# TouScruino-ui1-v0.net
KiCad netlist of a schematic drawn in EAGLE
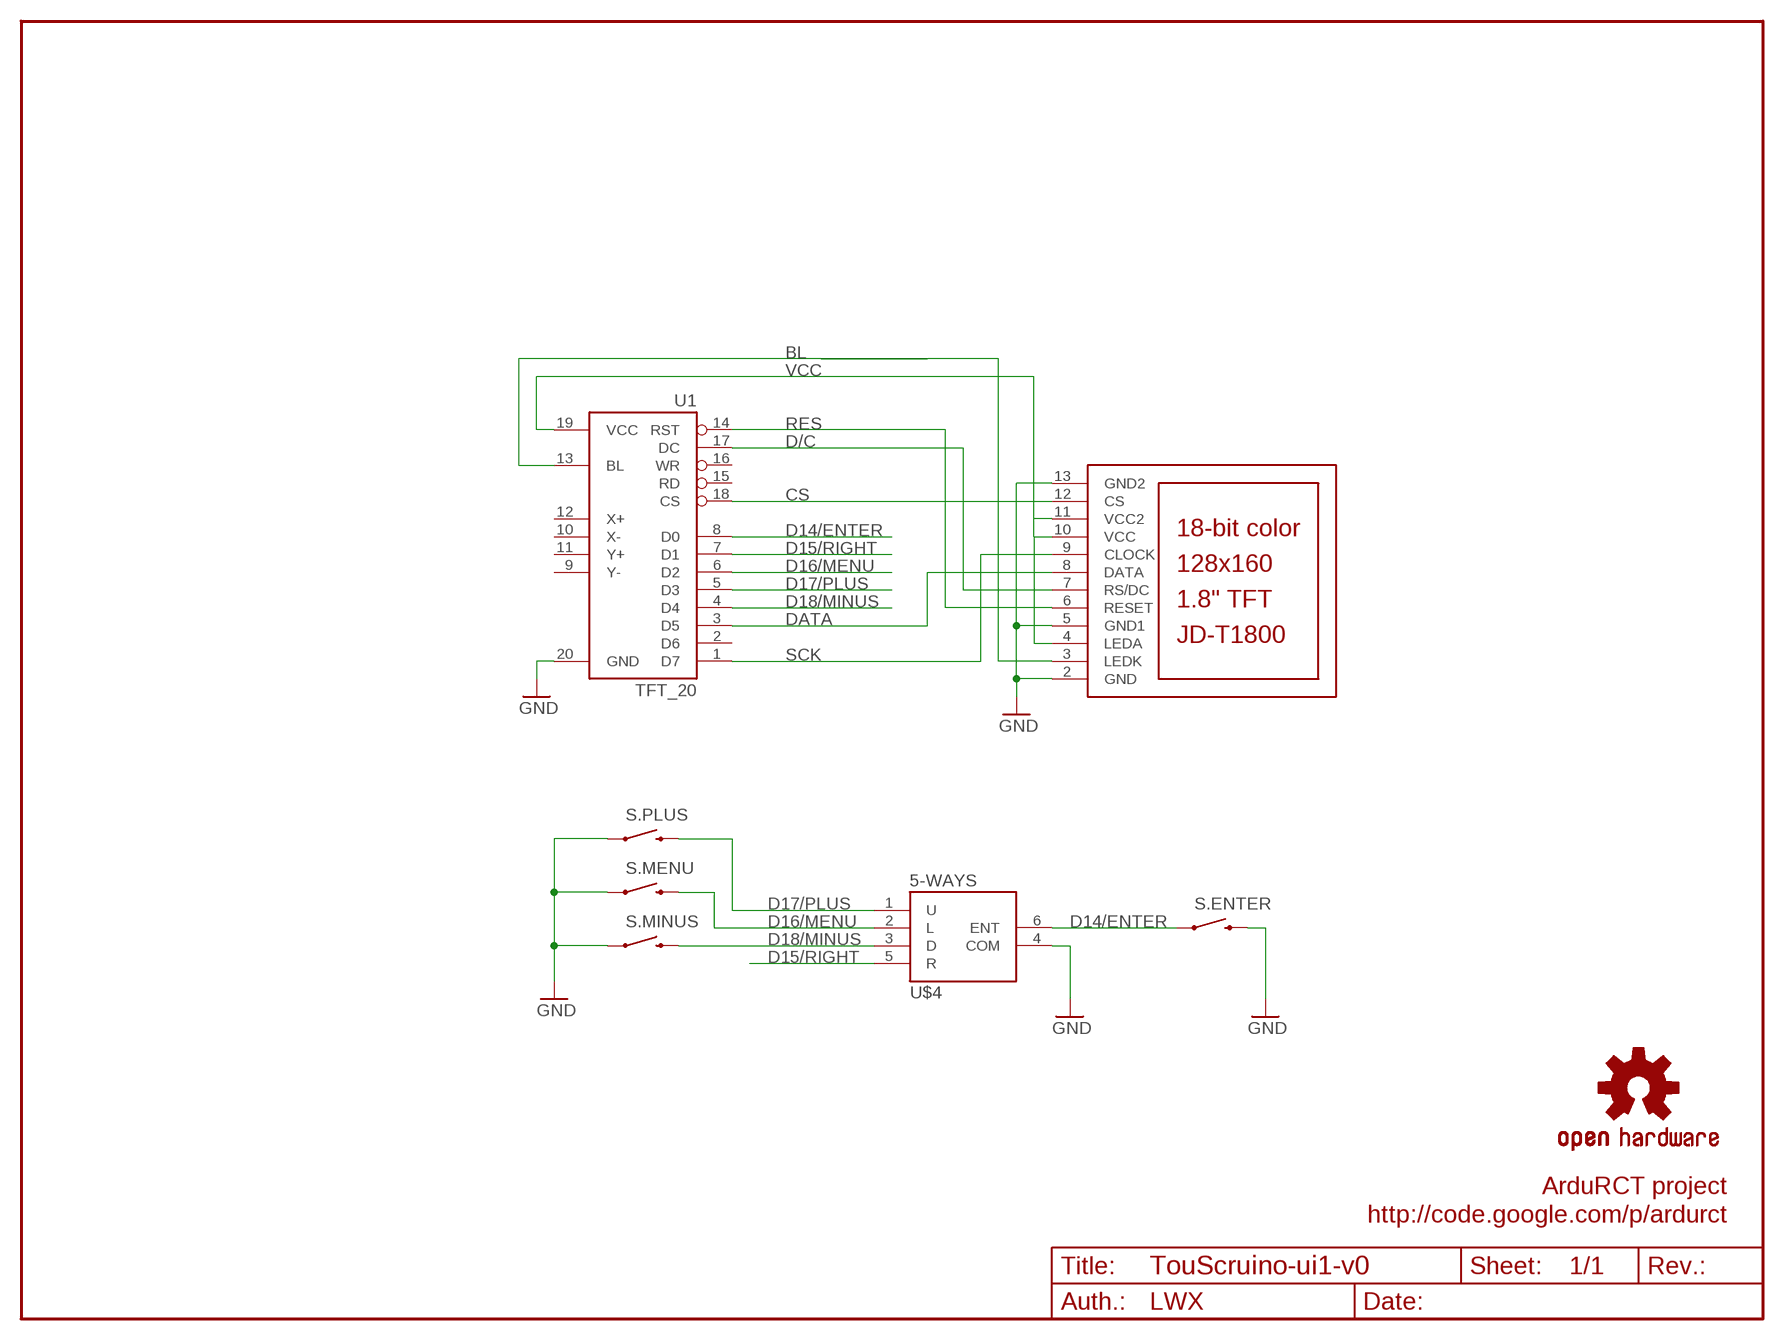
[diagram p0: schematic, sheet 1]

(export (version "E")
  (design (tool "Eeschema 10.0.6"))
  (components
    (comp (ref "LCD1")
      (value "JD-T1800")
      (footprint "eagle-import:JD-T1800")
      (libsource (lib "eagle-import") (part "JD-T1800"))
    )
    (comp (ref "S.ENTER")
      (value "SWITCH_SMD")
      (footprint "eagle-import:TACTILE_SWITCH_SMD")
      (libsource (lib "eagle-import") (part "SWITCH_SMD"))
    )
    (comp (ref "S.MENU")
      (value "SWITCH_SMD")
      (footprint "eagle-import:TACTILE_SWITCH_SMD")
      (libsource (lib "eagle-import") (part "SWITCH_SMD"))
    )
    (comp (ref "S.MINUS")
      (value "SWITCH_SMD")
      (footprint "eagle-import:TACTILE_SWITCH_SMD")
      (libsource (lib "eagle-import") (part "SWITCH_SMD"))
    )
    (comp (ref "S.PLUS")
      (value "SWITCH_SMD")
      (footprint "eagle-import:TACTILE_SWITCH_SMD")
      (libsource (lib "eagle-import") (part "SWITCH_SMD"))
    )
    (comp (ref "U$3")
      (value "OSHW-LOGOM")
      (footprint "eagle-import:OSHW-LOGO-M")
      (libsource (lib "eagle-import") (part "OSHW-LOGOM"))
    )
    (comp (ref "U$4")
      (value "5-WAYS")
      (footprint "eagle-import:5-WAYS_ALPS")
      (libsource (lib "eagle-import") (part "5-WAYS"))
    )
    (comp (ref "U1")
      (value "TFT_20")
      (footprint "eagle-import:TFT_20")
      (libsource (lib "eagle-import") (part "TFT_20"))
    )
  )
  (nets
    (net (code "1") (name "/BL") (class "Default")
      (node (ref "LCD1") (pin "3") (pinfunction "LEDK_3") (pintype "input"))
      (node (ref "U1") (pin "13") (pinfunction "BL_13") (pintype "bidirectional"))
    )
    (net (code "2") (name "/CS") (class "Default")
      (node (ref "LCD1") (pin "12") (pinfunction "CS_12") (pintype "input"))
      (node (ref "U1") (pin "18") (pinfunction "CS_18") (pintype "bidirectional"))
    )
    (net (code "3") (name "/D14{slash}ENTER") (class "Default")
      (node (ref "S.ENTER") (pin "1") (pinfunction "1_1") (pintype "passive"))
      (node (ref "U$4") (pin "6") (pinfunction "ENT_6") (pintype "bidirectional"))
      (node (ref "U1") (pin "8") (pinfunction "D0_8") (pintype "bidirectional"))
    )
    (net (code "4") (name "/D15{slash}RIGHT") (class "Default")
      (node (ref "U$4") (pin "5") (pinfunction "R_5") (pintype "bidirectional"))
      (node (ref "U1") (pin "7") (pinfunction "D1_7") (pintype "bidirectional"))
    )
    (net (code "5") (name "/D16{slash}MENU") (class "Default")
      (node (ref "S.MENU") (pin "3") (pinfunction "2_3") (pintype "passive"))
      (node (ref "U$4") (pin "2") (pinfunction "L_2") (pintype "bidirectional"))
      (node (ref "U1") (pin "6") (pinfunction "D2_6") (pintype "bidirectional"))
    )
    (net (code "6") (name "/D17{slash}PLUS") (class "Default")
      (node (ref "S.PLUS") (pin "3") (pinfunction "2_3") (pintype "passive"))
      (node (ref "U$4") (pin "1") (pinfunction "U_1") (pintype "bidirectional"))
      (node (ref "U1") (pin "5") (pinfunction "D3_5") (pintype "bidirectional"))
    )
    (net (code "7") (name "/D18{slash}MINUS") (class "Default")
      (node (ref "S.MINUS") (pin "3") (pinfunction "2_3") (pintype "passive"))
      (node (ref "U$4") (pin "3") (pinfunction "D_3") (pintype "bidirectional"))
      (node (ref "U1") (pin "4") (pinfunction "D4_4") (pintype "bidirectional"))
    )
    (net (code "8") (name "/DATA") (class "Default")
      (node (ref "LCD1") (pin "8") (pinfunction "DATA_8") (pintype "bidirectional"))
      (node (ref "U1") (pin "3") (pinfunction "D5_3") (pintype "bidirectional"))
    )
    (net (code "9") (name "/D{slash}C") (class "Default")
      (node (ref "LCD1") (pin "7") (pinfunction "RS/DC_7") (pintype "input"))
      (node (ref "U1") (pin "17") (pinfunction "DC_17") (pintype "bidirectional"))
    )
    (net (code "10") (name "/RES") (class "Default")
      (node (ref "LCD1") (pin "6") (pinfunction "RESET_6") (pintype "input"))
      (node (ref "U1") (pin "14") (pinfunction "RST_14") (pintype "bidirectional"))
    )
    (net (code "11") (name "/SCK") (class "Default")
      (node (ref "LCD1") (pin "9") (pinfunction "CLOCK_9") (pintype "input"))
      (node (ref "U1") (pin "1") (pinfunction "D7_1") (pintype "bidirectional"))
    )
    (net (code "12") (name "/VCC") (class "Default")
      (node (ref "LCD1") (pin "10") (pinfunction "VCC_10") (pintype "power_in"))
      (node (ref "LCD1") (pin "11") (pinfunction "VCC2_11") (pintype "power_in"))
      (node (ref "LCD1") (pin "4") (pinfunction "LEDA_4") (pintype "input"))
      (node (ref "U1") (pin "19") (pinfunction "VCC_19") (pintype "bidirectional"))
    )
    (net (code "13") (name "GND") (class "Default")
      (node (ref "LCD1") (pin "13") (pinfunction "GND2_13") (pintype "power_in"))
      (node (ref "LCD1") (pin "2") (pinfunction "GND_2") (pintype "power_in"))
      (node (ref "LCD1") (pin "5") (pinfunction "GND1_5") (pintype "power_in"))
      (node (ref "S.ENTER") (pin "3") (pinfunction "2_3") (pintype "passive"))
      (node (ref "S.MENU") (pin "1") (pinfunction "1_1") (pintype "passive"))
      (node (ref "S.MINUS") (pin "1") (pinfunction "1_1") (pintype "passive"))
      (node (ref "S.PLUS") (pin "1") (pinfunction "1_1") (pintype "passive"))
      (node (ref "U$4") (pin "4") (pinfunction "COM_4") (pintype "bidirectional"))
      (node (ref "U1") (pin "20") (pinfunction "GND_20") (pintype "bidirectional"))
    )
    (net (code "14") (name "unconnected-(U1-D6-Pad2)") (class "Default")
      (node (ref "U1") (pin "2") (pinfunction "D6_2") (pintype "bidirectional"))
    )
    (net (code "15") (name "unconnected-(U1-RD-Pad15)") (class "Default")
      (node (ref "U1") (pin "15") (pinfunction "RD_15") (pintype "bidirectional"))
    )
    (net (code "16") (name "unconnected-(U1-WR-Pad16)") (class "Default")
      (node (ref "U1") (pin "16") (pinfunction "WR_16") (pintype "bidirectional"))
    )
    (net (code "17") (name "unconnected-(U1-X+-Pad12)") (class "Default")
      (node (ref "U1") (pin "12") (pinfunction "X+_12") (pintype "bidirectional"))
    )
    (net (code "18") (name "unconnected-(U1-X--Pad10)") (class "Default")
      (node (ref "U1") (pin "10") (pinfunction "X-_10") (pintype "bidirectional"))
    )
    (net (code "19") (name "unconnected-(U1-Y+-Pad11)") (class "Default")
      (node (ref "U1") (pin "11") (pinfunction "Y+_11") (pintype "bidirectional"))
    )
    (net (code "20") (name "unconnected-(U1-Y--Pad9)") (class "Default")
      (node (ref "U1") (pin "9") (pinfunction "Y-_9") (pintype "bidirectional"))
    )
  )
)
